# AMS1117-ADJ.net
KiCad netlist of a schematic drawn in Altium Designer
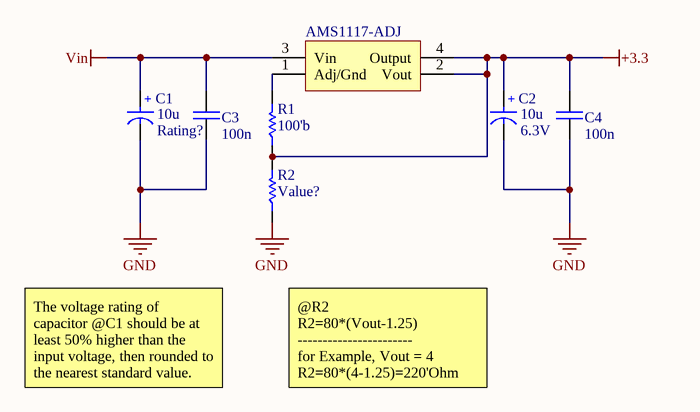
[diagram p0: AMS1117-ADJ.SchDoc]

(export (version "E")
  (design (tool "Eeschema 10.0.6"))
  (components
    (comp (ref "AMS1117-ADJ")
      (value "3.3V")
      (footprint "SOT223_M")
      (description "1'A Positive voltage regulator")
      (fields (field (name "VALIDATION") "Valid"))
      (libsource (lib "aKaReZa") (part "IC_Reg_AMS1117_3.3"))
    )
    (comp (ref "C1")
      (value "10u")
      (footprint "SMT_C_Tantalum_B")
      (description "Tantalum Capacitor,TAJ Series-SMD")
      (fields (field (name "RATING") "Rating?") (field (name "VALIDATION") "Valid"))
      (libsource (lib "aKaReZa") (part "Cap_Tantalum"))
    )
    (comp (ref "C2")
      (value "10u")
      (footprint "SMT_C_Tantalum_B")
      (description "Tantalum Capacitor,TAJ Series-SMD")
      (fields (field (name "RATING") "6.3V") (field (name "VALIDATION") "Valid"))
      (libsource (lib "aKaReZa") (part "Cap_Tantalum"))
    )
    (comp (ref "C3")
      (value "100n")
      (footprint "CAP 0805/2012")
      (description "Bipolar ceramic capacitor SMD")
      (fields (field (name "VALIDATION") "Valid"))
      (libsource (lib "aKaReZa") (part "Cap_Multi_SMD_100nF_0805"))
    )
    (comp (ref "C4")
      (value "100n")
      (footprint "CAP 0805/2012")
      (description "Bipolar ceramic capacitor SMD")
      (fields (field (name "VALIDATION") "Valid"))
      (libsource (lib "aKaReZa") (part "Cap_Multi_SMD_100nF_0805"))
    )
    (comp (ref "R1")
      (value "100'b")
      (footprint "RES 0805 (2012X06L)")
      (description "Resistor")
      (fields (field (name "VALIDATION") "Valid"))
      (libsource (lib "aKaReZa") (part "Res_SMD_0805"))
    )
    (comp (ref "R2")
      (value "Value?")
      (footprint "RES 0805 (2012X06L)")
      (description "Resistor")
      (fields (field (name "VALIDATION") "Valid"))
      (libsource (lib "aKaReZa") (part "Res_SMD_0805"))
    )
  )
  (nets
    (net (code "1") (name "+3.3") (class "Default")
      (node (ref "AMS1117-ADJ") (pin "2") (pinfunction "Vout_2") (pintype "passive"))
      (node (ref "AMS1117-ADJ") (pin "4") (pinfunction "Output_4") (pintype "passive"))
      (node (ref "C2") (pin "1") (pinfunction "+_1") (pintype "passive"))
      (node (ref "C4") (pin "1") (pinfunction "1_1") (pintype "passive"))
      (node (ref "R1") (pin "1") (pinfunction "1_1") (pintype "passive"))
      (node (ref "R2") (pin "2") (pinfunction "2_2") (pintype "passive"))
    )
    (net (code "2") (name "GND") (class "Default")
      (node (ref "C1") (pin "2") (pinfunction "-_2") (pintype "passive"))
      (node (ref "C2") (pin "2") (pinfunction "-_2") (pintype "passive"))
      (node (ref "C3") (pin "2") (pinfunction "2_2") (pintype "passive"))
      (node (ref "C4") (pin "2") (pinfunction "2_2") (pintype "passive"))
      (node (ref "R2") (pin "1") (pinfunction "1_1") (pintype "passive"))
    )
    (net (code "3") (name "Net-(AMS1117-ADJ-Adj{slash}Gnd)") (class "Default")
      (node (ref "AMS1117-ADJ") (pin "1") (pinfunction "Adj/Gnd_1") (pintype "passive"))
      (node (ref "R1") (pin "2") (pinfunction "2_2") (pintype "passive"))
    )
    (net (code "4") (name "Vin") (class "Default")
      (node (ref "AMS1117-ADJ") (pin "3") (pinfunction "Vin_3") (pintype "passive"))
      (node (ref "C1") (pin "1") (pinfunction "+_1") (pintype "passive"))
      (node (ref "C3") (pin "1") (pinfunction "1_1") (pintype "passive"))
    )
  )
)
